# bga614_lna.net
KiCad netlist of a schematic drawn in EAGLE
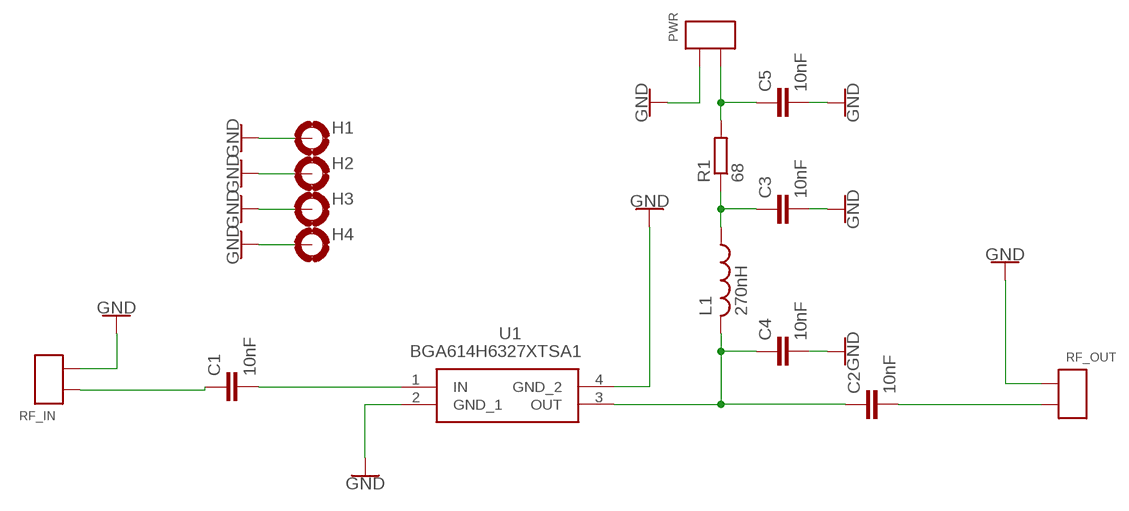
[diagram p0: schematic, sheet 1]

(export (version "E")
  (design (tool "Eeschema 10.0.6"))
  (components
    (comp (ref "C1")
      (value "10nF")
      (footprint "eagle-import:C0805")
      (libsource (lib "eagle-import") (part "C_0805_SMD"))
    )
    (comp (ref "C2")
      (value "10nF")
      (footprint "eagle-import:C0805")
      (libsource (lib "eagle-import") (part "C_0805_SMD"))
    )
    (comp (ref "C3")
      (value "10nF")
      (footprint "eagle-import:C0805")
      (libsource (lib "eagle-import") (part "C_0805_SMD"))
    )
    (comp (ref "C4")
      (value "10nF")
      (footprint "eagle-import:C0805")
      (libsource (lib "eagle-import") (part "C_0805_SMD"))
    )
    (comp (ref "C5")
      (value "10nF")
      (footprint "eagle-import:C0805")
      (libsource (lib "eagle-import") (part "C_0805_SMD"))
    )
    (comp (ref "H1")
      (value "MOUNT-PAD-ROUND3.0")
      (footprint "eagle-import:3,0-PAD")
      (libsource (lib "eagle-import") (part "MOUNT-PAD-ROUND3.0"))
    )
    (comp (ref "H2")
      (value "MOUNT-PAD-ROUND3.0")
      (footprint "eagle-import:3,0-PAD")
      (libsource (lib "eagle-import") (part "MOUNT-PAD-ROUND3.0"))
    )
    (comp (ref "H3")
      (value "MOUNT-PAD-ROUND3.0")
      (footprint "eagle-import:3,0-PAD")
      (libsource (lib "eagle-import") (part "MOUNT-PAD-ROUND3.0"))
    )
    (comp (ref "H4")
      (value "MOUNT-PAD-ROUND3.0")
      (footprint "eagle-import:3,0-PAD")
      (libsource (lib "eagle-import") (part "MOUNT-PAD-ROUND3.0"))
    )
    (comp (ref "L1")
      (value "270nH")
      (footprint "eagle-import:M0805")
      (libsource (lib "eagle-import") (part "L_0805_PTH"))
    )
    (comp (ref "PWR")
      (value "2X_SMD_PTH_PIN")
      (footprint "eagle-import:2X_SMD_PTH")
      (libsource (lib "eagle-import") (part "2X_SMD_PTH_PIN"))
    )
    (comp (ref "R1")
      (value "68")
      (footprint "eagle-import:R0805W")
      (libsource (lib "eagle-import") (part "R_0805_SMD"))
    )
    (comp (ref "RF_IN")
      (value "2X_SMD_PTH_PIN")
      (footprint "eagle-import:2X_SMD_PTH")
      (libsource (lib "eagle-import") (part "2X_SMD_PTH_PIN"))
    )
    (comp (ref "RF_OUT")
      (value "2X_SMD_PTH_PIN")
      (footprint "eagle-import:2X_SMD_PTH")
      (libsource (lib "eagle-import") (part "2X_SMD_PTH_PIN"))
    )
    (comp (ref "U1")
      (value "BGA614H6327XTSA1")
      (footprint "eagle-import:BGA614H6327XTSA1")
      (fields (field (name "MOUSER_PART_NUMBER") "726-BGA614H6327XTSA1"))
      (libsource (lib "eagle-import") (part "BGA614H6327XTSA1"))
    )
  )
  (nets
    (net (code "1") (name "GND") (class "Default")
      (node (ref "C3") (pin "2") (pinfunction "2_2") (pintype "passive"))
      (node (ref "C4") (pin "2") (pinfunction "2_2") (pintype "passive"))
      (node (ref "C5") (pin "2") (pinfunction "2_2") (pintype "passive"))
      (node (ref "H1") (pin "B3,0") (pinfunction "MOUNT_B3,0") (pintype "passive"))
      (node (ref "H2") (pin "B3,0") (pinfunction "MOUNT_B3,0") (pintype "passive"))
      (node (ref "H3") (pin "B3,0") (pinfunction "MOUNT_B3,0") (pintype "passive"))
      (node (ref "H4") (pin "B3,0") (pinfunction "MOUNT_B3,0") (pintype "passive"))
      (node (ref "PWR") (pin "P$1") (pinfunction "PIN0_P$1") (pintype "bidirectional"))
      (node (ref "PWR") (pin "T$1") (pinfunction "PIN0_T$1") (pintype "bidirectional"))
      (node (ref "RF_IN") (pin "P$2") (pinfunction "PIN1_P$2") (pintype "bidirectional"))
      (node (ref "RF_IN") (pin "T$2") (pinfunction "PIN1_T$2") (pintype "bidirectional"))
      (node (ref "RF_OUT") (pin "P$1") (pinfunction "PIN0_P$1") (pintype "bidirectional"))
      (node (ref "RF_OUT") (pin "T$1") (pinfunction "PIN0_T$1") (pintype "bidirectional"))
      (node (ref "U1") (pin "2") (pinfunction "GND_1_2") (pintype "bidirectional"))
      (node (ref "U1") (pin "4") (pinfunction "GND_2_4") (pintype "bidirectional"))
    )
    (net (code "2") (name "Net-(C1-Pad1)") (class "Default")
      (node (ref "C1") (pin "1") (pinfunction "1_1") (pintype "passive"))
      (node (ref "RF_IN") (pin "P$1") (pinfunction "PIN0_P$1") (pintype "bidirectional"))
      (node (ref "RF_IN") (pin "T$1") (pinfunction "PIN0_T$1") (pintype "bidirectional"))
    )
    (net (code "3") (name "Net-(C2-Pad2)") (class "Default")
      (node (ref "C2") (pin "2") (pinfunction "2_2") (pintype "passive"))
      (node (ref "RF_OUT") (pin "P$2") (pinfunction "PIN1_P$2") (pintype "bidirectional"))
      (node (ref "RF_OUT") (pin "T$2") (pinfunction "PIN1_T$2") (pintype "bidirectional"))
    )
    (net (code "4") (name "Net-(C3-Pad1)") (class "Default")
      (node (ref "C3") (pin "1") (pinfunction "1_1") (pintype "passive"))
      (node (ref "L1") (pin "1") (pinfunction "1_1") (pintype "passive"))
      (node (ref "L1") (pin "P$1") (pinfunction "1_P$1") (pintype "passive"))
      (node (ref "R1") (pin "1") (pinfunction "1_1") (pintype "passive"))
    )
    (net (code "5") (name "Net-(C5-Pad1)") (class "Default")
      (node (ref "C5") (pin "1") (pinfunction "1_1") (pintype "passive"))
      (node (ref "PWR") (pin "P$2") (pinfunction "PIN1_P$2") (pintype "bidirectional"))
      (node (ref "PWR") (pin "T$2") (pinfunction "PIN1_T$2") (pintype "bidirectional"))
      (node (ref "R1") (pin "2") (pinfunction "2_2") (pintype "passive"))
    )
    (net (code "6") (name "Net-(U1-IN)") (class "Default")
      (node (ref "C1") (pin "2") (pinfunction "2_2") (pintype "passive"))
      (node (ref "U1") (pin "1") (pinfunction "IN_1") (pintype "bidirectional"))
    )
    (net (code "7") (name "Net-(U1-OUT)") (class "Default")
      (node (ref "C2") (pin "1") (pinfunction "1_1") (pintype "passive"))
      (node (ref "C4") (pin "1") (pinfunction "1_1") (pintype "passive"))
      (node (ref "L1") (pin "2") (pinfunction "2_2") (pintype "passive"))
      (node (ref "L1") (pin "P$2") (pinfunction "2_P$2") (pintype "passive"))
      (node (ref "U1") (pin "3") (pinfunction "OUT_3") (pintype "bidirectional"))
    )
  )
)
